# untitled_1.net
KiCad netlist of a schematic drawn in EAGLE
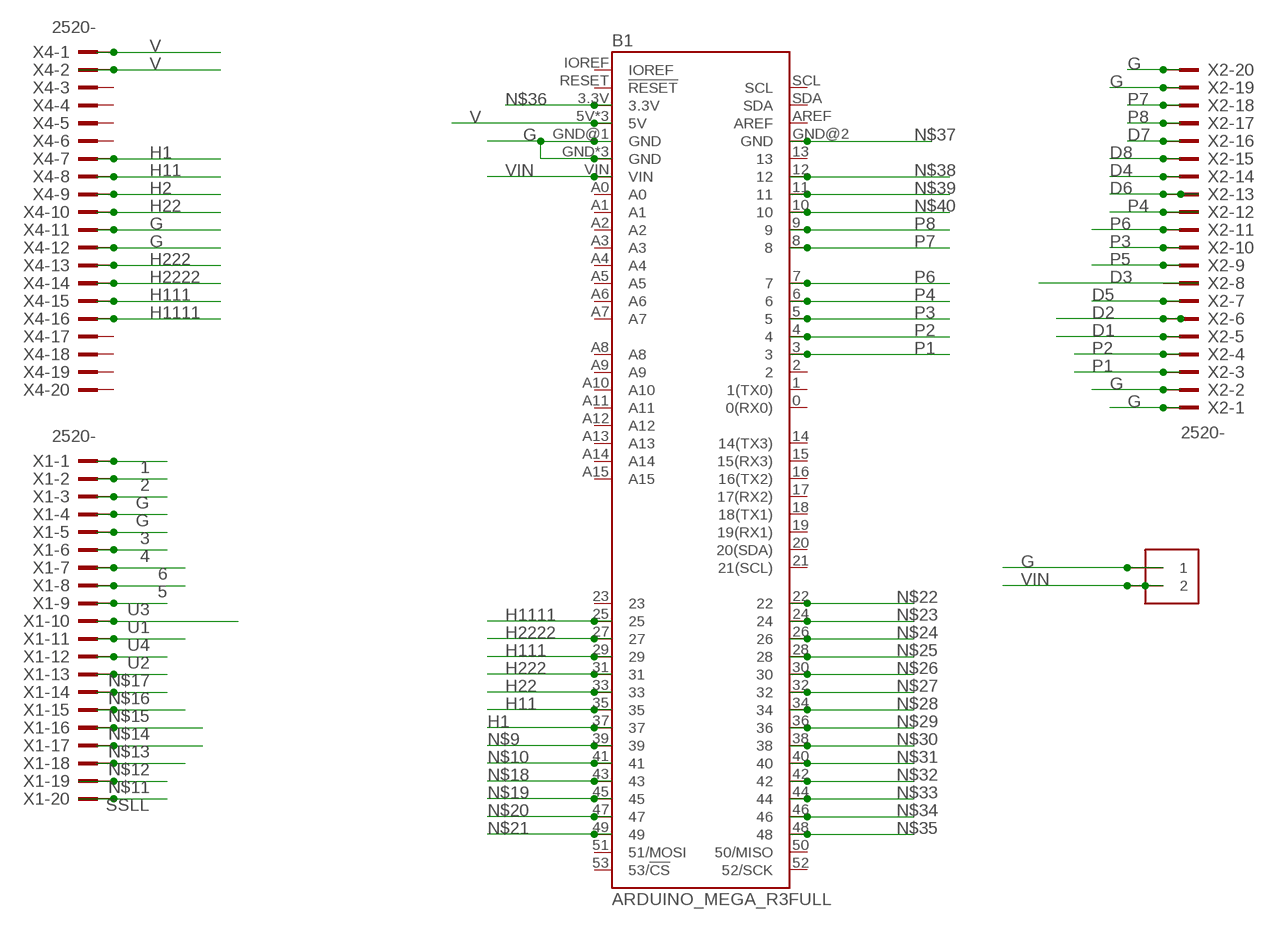
[diagram p0: schematic, sheet 1]

(export (version "E")
  (design (tool "Eeschema 10.0.6"))
  (components
    (comp (ref "B1")
      (value "ARDUINO_MEGA_R3FULL")
      (footprint "eagle-import:ARDUINO_MEGA_NO_SILK")
      (libsource (lib "eagle-import") (part "ARDUINO_MEGA_R3FULL"))
    )
    (comp (ref "J1")
      (value "1X2-3.5MM")
      (footprint "eagle-import:1X2-3.5MM")
      (libsource (lib "eagle-import") (part "1X2-3.5MM"))
    )
    (comp (ref "X1")
      (value "2520-")
      (footprint "eagle-import:PAK100_2500-20")
      (libsource (lib "eagle-import") (part "con-3m_119_2520-"))
    )
    (comp (ref "X2")
      (value "2520-")
      (footprint "eagle-import:PAK100_2500-20")
      (libsource (lib "eagle-import") (part "con-3m_119_2520-"))
    )
    (comp (ref "X4")
      (value "2520-")
      (footprint "eagle-import:PAK100_2500-20")
      (libsource (lib "eagle-import") (part "2520-"))
    )
  )
  (nets
    (net (code "1") (name "/1") (class "Default")
      (node (ref "X1") (pin "1") (pinfunction "KL_1") (pintype "passive"))
    )
    (net (code "2") (name "/2") (class "Default")
      (node (ref "X1") (pin "2") (pinfunction "KL_2") (pintype "passive"))
    )
    (net (code "3") (name "/3") (class "Default")
      (node (ref "X1") (pin "5") (pinfunction "KL_5") (pintype "passive"))
    )
    (net (code "4") (name "/4") (class "Default")
      (node (ref "X1") (pin "6") (pinfunction "KL_6") (pintype "passive"))
    )
    (net (code "5") (name "/5") (class "Default")
      (node (ref "X1") (pin "8") (pinfunction "KL_8") (pintype "passive"))
    )
    (net (code "6") (name "/6") (class "Default")
      (node (ref "X1") (pin "7") (pinfunction "KL_7") (pintype "passive"))
    )
    (net (code "7") (name "/D1") (class "Default")
      (node (ref "X2") (pin "5") (pinfunction "KL_5") (pintype "passive"))
    )
    (net (code "8") (name "/D2") (class "Default")
      (node (ref "X2") (pin "6") (pinfunction "KL_6") (pintype "passive"))
    )
    (net (code "9") (name "/D3") (class "Default")
      (node (ref "X2") (pin "8") (pinfunction "KL_8") (pintype "passive"))
    )
    (net (code "10") (name "/D4") (class "Default")
      (node (ref "X2") (pin "14") (pinfunction "KL_14") (pintype "passive"))
    )
    (net (code "11") (name "/D5") (class "Default")
      (node (ref "X2") (pin "7") (pinfunction "KL_7") (pintype "passive"))
    )
    (net (code "12") (name "/D6") (class "Default")
      (node (ref "X2") (pin "13") (pinfunction "KL_13") (pintype "passive"))
    )
    (net (code "13") (name "/D7") (class "Default")
      (node (ref "X2") (pin "16") (pinfunction "KL_16") (pintype "passive"))
    )
    (net (code "14") (name "/D8") (class "Default")
      (node (ref "X2") (pin "15") (pinfunction "KL_15") (pintype "passive"))
    )
    (net (code "15") (name "/G") (class "Default")
      (node (ref "B1") (pin "GND") (pinfunction "GND_GND") (pintype "bidirectional"))
      (node (ref "B1") (pin "GND@1") (pinfunction "GND_GND@1") (pintype "bidirectional"))
      (node (ref "B1") (pin "GND@3") (pinfunction "GND_GND@3") (pintype "bidirectional"))
      (node (ref "B1") (pin "GND@4") (pinfunction "GND_GND@4") (pintype "bidirectional"))
      (node (ref "J1") (pin "1") (pinfunction "1_1") (pintype "passive"))
      (node (ref "X1") (pin "3") (pinfunction "KL_3") (pintype "passive"))
      (node (ref "X1") (pin "4") (pinfunction "KL_4") (pintype "passive"))
      (node (ref "X2") (pin "1") (pinfunction "KL_1") (pintype "passive"))
      (node (ref "X2") (pin "19") (pinfunction "KL_19") (pintype "passive"))
      (node (ref "X2") (pin "2") (pinfunction "KL_2") (pintype "passive"))
      (node (ref "X2") (pin "20") (pinfunction "KL_20") (pintype "passive"))
      (node (ref "X4") (pin "11") (pinfunction "KL_11") (pintype "passive"))
      (node (ref "X4") (pin "12") (pinfunction "KL_12") (pintype "passive"))
    )
    (net (code "16") (name "/H1") (class "Default")
      (node (ref "B1") (pin "37") (pinfunction "37_37") (pintype "bidirectional"))
      (node (ref "X4") (pin "7") (pinfunction "KL_7") (pintype "passive"))
    )
    (net (code "17") (name "/H2") (class "Default")
      (node (ref "X4") (pin "9") (pinfunction "KL_9") (pintype "passive"))
    )
    (net (code "18") (name "/H11") (class "Default")
      (node (ref "B1") (pin "35") (pinfunction "35_35") (pintype "bidirectional"))
      (node (ref "X4") (pin "8") (pinfunction "KL_8") (pintype "passive"))
    )
    (net (code "19") (name "/H22") (class "Default")
      (node (ref "B1") (pin "33") (pinfunction "33_33") (pintype "bidirectional"))
      (node (ref "X4") (pin "10") (pinfunction "KL_10") (pintype "passive"))
    )
    (net (code "20") (name "/H111") (class "Default")
      (node (ref "B1") (pin "29") (pinfunction "29_29") (pintype "bidirectional"))
      (node (ref "X4") (pin "15") (pinfunction "KL_15") (pintype "passive"))
    )
    (net (code "21") (name "/H222") (class "Default")
      (node (ref "B1") (pin "31") (pinfunction "31_31") (pintype "bidirectional"))
      (node (ref "X4") (pin "13") (pinfunction "KL_13") (pintype "passive"))
    )
    (net (code "22") (name "/H1111") (class "Default")
      (node (ref "B1") (pin "25") (pinfunction "25_25") (pintype "bidirectional"))
      (node (ref "X4") (pin "16") (pinfunction "KL_16") (pintype "passive"))
    )
    (net (code "23") (name "/H2222") (class "Default")
      (node (ref "B1") (pin "27") (pinfunction "27_27") (pintype "bidirectional"))
      (node (ref "X4") (pin "14") (pinfunction "KL_14") (pintype "passive"))
    )
    (net (code "24") (name "/N$9") (class "Default")
      (node (ref "B1") (pin "39") (pinfunction "39_39") (pintype "bidirectional"))
    )
    (net (code "25") (name "/N$10") (class "Default")
      (node (ref "B1") (pin "41") (pinfunction "41_41") (pintype "bidirectional"))
    )
    (net (code "26") (name "/N$11") (class "Default")
      (node (ref "X1") (pin "19") (pinfunction "KL_19") (pintype "passive"))
    )
    (net (code "27") (name "/N$12") (class "Default")
      (node (ref "X1") (pin "18") (pinfunction "KL_18") (pintype "passive"))
    )
    (net (code "28") (name "/N$13") (class "Default")
      (node (ref "X1") (pin "17") (pinfunction "KL_17") (pintype "passive"))
    )
    (net (code "29") (name "/N$14") (class "Default")
      (node (ref "X1") (pin "16") (pinfunction "KL_16") (pintype "passive"))
    )
    (net (code "30") (name "/N$15") (class "Default")
      (node (ref "X1") (pin "15") (pinfunction "KL_15") (pintype "passive"))
    )
    (net (code "31") (name "/N$16") (class "Default")
      (node (ref "X1") (pin "14") (pinfunction "KL_14") (pintype "passive"))
    )
    (net (code "32") (name "/N$17") (class "Default")
      (node (ref "X1") (pin "13") (pinfunction "KL_13") (pintype "passive"))
    )
    (net (code "33") (name "/N$18") (class "Default")
      (node (ref "B1") (pin "43") (pinfunction "43_43") (pintype "bidirectional"))
    )
    (net (code "34") (name "/N$19") (class "Default")
      (node (ref "B1") (pin "45") (pinfunction "45_45") (pintype "bidirectional"))
    )
    (net (code "35") (name "/N$20") (class "Default")
      (node (ref "B1") (pin "47") (pinfunction "47_47") (pintype "bidirectional"))
    )
    (net (code "36") (name "/N$21") (class "Default")
      (node (ref "B1") (pin "49") (pinfunction "49_49") (pintype "bidirectional"))
    )
    (net (code "37") (name "/N$22") (class "Default")
      (node (ref "B1") (pin "22") (pinfunction "22_22") (pintype "bidirectional"))
    )
    (net (code "38") (name "/N$23") (class "Default")
      (node (ref "B1") (pin "24") (pinfunction "24_24") (pintype "bidirectional"))
    )
    (net (code "39") (name "/N$24") (class "Default")
      (node (ref "B1") (pin "26") (pinfunction "26_26") (pintype "bidirectional"))
    )
    (net (code "40") (name "/N$25") (class "Default")
      (node (ref "B1") (pin "28") (pinfunction "28_28") (pintype "bidirectional"))
    )
    (net (code "41") (name "/N$26") (class "Default")
      (node (ref "B1") (pin "30") (pinfunction "30_30") (pintype "bidirectional"))
    )
    (net (code "42") (name "/N$27") (class "Default")
      (node (ref "B1") (pin "32") (pinfunction "32_32") (pintype "bidirectional"))
    )
    (net (code "43") (name "/N$28") (class "Default")
      (node (ref "B1") (pin "34") (pinfunction "34_34") (pintype "bidirectional"))
    )
    (net (code "44") (name "/N$29") (class "Default")
      (node (ref "B1") (pin "36") (pinfunction "36_36") (pintype "bidirectional"))
    )
    (net (code "45") (name "/N$30") (class "Default")
      (node (ref "B1") (pin "38") (pinfunction "38_38") (pintype "bidirectional"))
    )
    (net (code "46") (name "/N$31") (class "Default")
      (node (ref "B1") (pin "40") (pinfunction "40_40") (pintype "bidirectional"))
    )
    (net (code "47") (name "/N$32") (class "Default")
      (node (ref "B1") (pin "42") (pinfunction "42_42") (pintype "bidirectional"))
    )
    (net (code "48") (name "/N$33") (class "Default")
      (node (ref "B1") (pin "44") (pinfunction "44_44") (pintype "bidirectional"))
    )
    (net (code "49") (name "/N$34") (class "Default")
      (node (ref "B1") (pin "46") (pinfunction "46_46") (pintype "bidirectional"))
    )
    (net (code "50") (name "/N$35") (class "Default")
      (node (ref "B1") (pin "48") (pinfunction "48_48") (pintype "bidirectional"))
    )
    (net (code "51") (name "/N$36") (class "Default")
      (node (ref "B1") (pin "3.3V") (pinfunction "3.3V_3.3V") (pintype "bidirectional"))
    )
    (net (code "52") (name "/N$37") (class "Default")
      (node (ref "B1") (pin "GND@2") (pinfunction "GND_GND@2") (pintype "bidirectional"))
    )
    (net (code "53") (name "/N$38") (class "Default")
      (node (ref "B1") (pin "12") (pinfunction "12_12") (pintype "bidirectional"))
    )
    (net (code "54") (name "/N$39") (class "Default")
      (node (ref "B1") (pin "11") (pinfunction "11_11") (pintype "bidirectional"))
    )
    (net (code "55") (name "/N$40") (class "Default")
      (node (ref "B1") (pin "10") (pinfunction "10_10") (pintype "bidirectional"))
    )
    (net (code "56") (name "/P1") (class "Default")
      (node (ref "B1") (pin "3") (pinfunction "3_3") (pintype "bidirectional"))
      (node (ref "X2") (pin "3") (pinfunction "KL_3") (pintype "passive"))
    )
    (net (code "57") (name "/P2") (class "Default")
      (node (ref "B1") (pin "4") (pinfunction "4_4") (pintype "bidirectional"))
      (node (ref "X2") (pin "4") (pinfunction "KL_4") (pintype "passive"))
    )
    (net (code "58") (name "/P3") (class "Default")
      (node (ref "B1") (pin "5") (pinfunction "5_5") (pintype "bidirectional"))
      (node (ref "X2") (pin "10") (pinfunction "KL_10") (pintype "passive"))
    )
    (net (code "59") (name "/P4") (class "Default")
      (node (ref "B1") (pin "6") (pinfunction "6_6") (pintype "bidirectional"))
      (node (ref "X2") (pin "12") (pinfunction "KL_12") (pintype "passive"))
    )
    (net (code "60") (name "/P5") (class "Default")
      (node (ref "X2") (pin "9") (pinfunction "KL_9") (pintype "passive"))
    )
    (net (code "61") (name "/P6") (class "Default")
      (node (ref "B1") (pin "7") (pinfunction "7_7") (pintype "bidirectional"))
      (node (ref "X2") (pin "11") (pinfunction "KL_11") (pintype "passive"))
    )
    (net (code "62") (name "/P7") (class "Default")
      (node (ref "B1") (pin "8") (pinfunction "8_8") (pintype "bidirectional"))
      (node (ref "X2") (pin "18") (pinfunction "KL_18") (pintype "passive"))
    )
    (net (code "63") (name "/P8") (class "Default")
      (node (ref "B1") (pin "9") (pinfunction "9_9") (pintype "bidirectional"))
      (node (ref "X2") (pin "17") (pinfunction "KL_17") (pintype "passive"))
    )
    (net (code "64") (name "/SSLL") (class "Default")
      (node (ref "X1") (pin "20") (pinfunction "KL_20") (pintype "passive"))
    )
    (net (code "65") (name "/U1") (class "Default")
      (node (ref "X1") (pin "10") (pinfunction "KL_10") (pintype "passive"))
    )
    (net (code "66") (name "/U2") (class "Default")
      (node (ref "X1") (pin "12") (pinfunction "KL_12") (pintype "passive"))
    )
    (net (code "67") (name "/U3") (class "Default")
      (node (ref "X1") (pin "9") (pinfunction "KL_9") (pintype "passive"))
    )
    (net (code "68") (name "/U4") (class "Default")
      (node (ref "X1") (pin "11") (pinfunction "KL_11") (pintype "passive"))
    )
    (net (code "69") (name "/V") (class "Default")
      (node (ref "B1") (pin "5V") (pinfunction "5V_5V") (pintype "bidirectional"))
      (node (ref "B1") (pin "5V@1") (pinfunction "5V_5V@1") (pintype "bidirectional"))
      (node (ref "B1") (pin "5V@2") (pinfunction "5V_5V@2") (pintype "bidirectional"))
      (node (ref "X4") (pin "1") (pinfunction "KL_1") (pintype "passive"))
      (node (ref "X4") (pin "2") (pinfunction "KL_2") (pintype "passive"))
    )
    (net (code "70") (name "/VIN") (class "Default")
      (node (ref "B1") (pin "VIN") (pinfunction "VIN_VIN") (pintype "bidirectional"))
      (node (ref "J1") (pin "2") (pinfunction "2_2") (pintype "passive"))
    )
    (net (code "71") (name "unconnected-(B1-0(RX0)-Pad0)") (class "Default")
      (node (ref "B1") (pin "0") (pinfunction "0(RX0)_0") (pintype "bidirectional"))
    )
    (net (code "72") (name "unconnected-(B1-1(TX0)-Pad1)") (class "Default")
      (node (ref "B1") (pin "1") (pinfunction "1(TX0)_1") (pintype "bidirectional"))
    )
    (net (code "73") (name "unconnected-(B1-14(TX3)-Pad14)") (class "Default")
      (node (ref "B1") (pin "14") (pinfunction "14(TX3)_14") (pintype "bidirectional"))
    )
    (net (code "74") (name "unconnected-(B1-15(RX3)-Pad15)") (class "Default")
      (node (ref "B1") (pin "15") (pinfunction "15(RX3)_15") (pintype "bidirectional"))
    )
    (net (code "75") (name "unconnected-(B1-16(TX2)-Pad16)") (class "Default")
      (node (ref "B1") (pin "16") (pinfunction "16(TX2)_16") (pintype "bidirectional"))
    )
    (net (code "76") (name "unconnected-(B1-17(RX2)-Pad17)") (class "Default")
      (node (ref "B1") (pin "17") (pinfunction "17(RX2)_17") (pintype "bidirectional"))
    )
    (net (code "77") (name "unconnected-(B1-18(TX1)-Pad18)") (class "Default")
      (node (ref "B1") (pin "18") (pinfunction "18(TX1)_18") (pintype "bidirectional"))
    )
    (net (code "78") (name "unconnected-(B1-19(RX1)-Pad19)") (class "Default")
      (node (ref "B1") (pin "19") (pinfunction "19(RX1)_19") (pintype "bidirectional"))
    )
    (net (code "79") (name "unconnected-(B1-20(SDA)-Pad20)") (class "Default")
      (node (ref "B1") (pin "20") (pinfunction "20(SDA)_20") (pintype "bidirectional"))
    )
    (net (code "80") (name "unconnected-(B1-21(SCL)-Pad21)") (class "Default")
      (node (ref "B1") (pin "21") (pinfunction "21(SCL)_21") (pintype "bidirectional"))
    )
    (net (code "81") (name "unconnected-(B1-50{slash}MISO-Pad50)") (class "Default")
      (node (ref "B1") (pin "50") (pinfunction "50/MISO_50") (pintype "bidirectional"))
    )
    (net (code "82") (name "unconnected-(B1-51{slash}MOSI-Pad51)") (class "Default")
      (node (ref "B1") (pin "51") (pinfunction "51/MOSI_51") (pintype "bidirectional"))
    )
    (net (code "83") (name "unconnected-(B1-52{slash}SCK-Pad52)") (class "Default")
      (node (ref "B1") (pin "52") (pinfunction "52/SCK_52") (pintype "bidirectional"))
    )
    (net (code "84") (name "unconnected-(B1-53{slash}~{CS}-Pad53)") (class "Default")
      (node (ref "B1") (pin "53") (pinfunction "53/~{CS}_53") (pintype "bidirectional"))
    )
    (net (code "85") (name "unconnected-(B1-Pad2)") (class "Default")
      (node (ref "B1") (pin "2") (pinfunction "2_2") (pintype "bidirectional"))
    )
    (net (code "86") (name "unconnected-(B1-Pad13)") (class "Default")
      (node (ref "B1") (pin "13") (pinfunction "13_13") (pintype "bidirectional"))
    )
    (net (code "87") (name "unconnected-(B1-Pad23)") (class "Default")
      (node (ref "B1") (pin "23") (pinfunction "23_23") (pintype "bidirectional"))
    )
    (net (code "88") (name "unconnected-(B1-PadA0)") (class "Default")
      (node (ref "B1") (pin "A0") (pinfunction "A0_A0") (pintype "bidirectional"))
    )
    (net (code "89") (name "unconnected-(B1-PadA1)") (class "Default")
      (node (ref "B1") (pin "A1") (pinfunction "A1_A1") (pintype "bidirectional"))
    )
    (net (code "90") (name "unconnected-(B1-PadA2)") (class "Default")
      (node (ref "B1") (pin "A2") (pinfunction "A2_A2") (pintype "bidirectional"))
    )
    (net (code "91") (name "unconnected-(B1-PadA3)") (class "Default")
      (node (ref "B1") (pin "A3") (pinfunction "A3_A3") (pintype "bidirectional"))
    )
    (net (code "92") (name "unconnected-(B1-PadA4)") (class "Default")
      (node (ref "B1") (pin "A4") (pinfunction "A4_A4") (pintype "bidirectional"))
    )
    (net (code "93") (name "unconnected-(B1-PadA5)") (class "Default")
      (node (ref "B1") (pin "A5") (pinfunction "A5_A5") (pintype "bidirectional"))
    )
    (net (code "94") (name "unconnected-(B1-PadA6)") (class "Default")
      (node (ref "B1") (pin "A6") (pinfunction "A6_A6") (pintype "bidirectional"))
    )
    (net (code "95") (name "unconnected-(B1-PadA7)") (class "Default")
      (node (ref "B1") (pin "A7") (pinfunction "A7_A7") (pintype "bidirectional"))
    )
    (net (code "96") (name "unconnected-(B1-PadA8)") (class "Default")
      (node (ref "B1") (pin "A8") (pinfunction "A8_A8") (pintype "bidirectional"))
    )
    (net (code "97") (name "unconnected-(B1-PadA9)") (class "Default")
      (node (ref "B1") (pin "A9") (pinfunction "A9_A9") (pintype "bidirectional"))
    )
    (net (code "98") (name "unconnected-(B1-PadA10)") (class "Default")
      (node (ref "B1") (pin "A10") (pinfunction "A10_A10") (pintype "bidirectional"))
    )
    (net (code "99") (name "unconnected-(B1-PadA11)") (class "Default")
      (node (ref "B1") (pin "A11") (pinfunction "A11_A11") (pintype "bidirectional"))
    )
    (net (code "100") (name "unconnected-(B1-PadA12)") (class "Default")
      (node (ref "B1") (pin "A12") (pinfunction "A12_A12") (pintype "bidirectional"))
    )
    (net (code "101") (name "unconnected-(B1-PadA13)") (class "Default")
      (node (ref "B1") (pin "A13") (pinfunction "A13_A13") (pintype "bidirectional"))
    )
    (net (code "102") (name "unconnected-(B1-PadA14)") (class "Default")
      (node (ref "B1") (pin "A14") (pinfunction "A14_A14") (pintype "bidirectional"))
    )
    (net (code "103") (name "unconnected-(B1-PadA15)") (class "Default")
      (node (ref "B1") (pin "A15") (pinfunction "A15_A15") (pintype "bidirectional"))
    )
    (net (code "104") (name "unconnected-(B1-PadAREF)") (class "Default")
      (node (ref "B1") (pin "AREF") (pinfunction "AREF_AREF") (pintype "bidirectional"))
    )
    (net (code "105") (name "unconnected-(B1-PadIOREF)") (class "Default")
      (node (ref "B1") (pin "IOREF") (pinfunction "IOREF_IOREF") (pintype "bidirectional"))
    )
    (net (code "106") (name "unconnected-(B1-PadSCL)") (class "Default")
      (node (ref "B1") (pin "SCL") (pinfunction "SCL_SCL") (pintype "bidirectional"))
    )
    (net (code "107") (name "unconnected-(B1-PadSDA)") (class "Default")
      (node (ref "B1") (pin "SDA") (pinfunction "SDA_SDA") (pintype "bidirectional"))
    )
    (net (code "108") (name "unconnected-(B1-~{RESET}-PadRESET)") (class "Default")
      (node (ref "B1") (pin "RESET") (pinfunction "~{RESET}_RESET") (pintype "bidirectional"))
    )
    (net (code "109") (name "unconnected-(X4I-KL-Pad17)") (class "Default")
      (node (ref "X4") (pin "17") (pinfunction "KL_17") (pintype "passive"))
    )
    (net (code "110") (name "unconnected-(X4J-KL-Pad18)") (class "Default")
      (node (ref "X4") (pin "18") (pinfunction "KL_18") (pintype "passive"))
    )
    (net (code "111") (name "unconnected-(X4K-KL-Pad19)") (class "Default")
      (node (ref "X4") (pin "19") (pinfunction "KL_19") (pintype "passive"))
    )
    (net (code "112") (name "unconnected-(X4M-KL-Pad20)") (class "Default")
      (node (ref "X4") (pin "20") (pinfunction "KL_20") (pintype "passive"))
    )
    (net (code "113") (name "unconnected-(X4N-KL-Pad3)") (class "Default")
      (node (ref "X4") (pin "3") (pinfunction "KL_3") (pintype "passive"))
    )
    (net (code "114") (name "unconnected-(X4O-KL-Pad4)") (class "Default")
      (node (ref "X4") (pin "4") (pinfunction "KL_4") (pintype "passive"))
    )
    (net (code "115") (name "unconnected-(X4P-KL-Pad5)") (class "Default")
      (node (ref "X4") (pin "5") (pinfunction "KL_5") (pintype "passive"))
    )
    (net (code "116") (name "unconnected-(X4Q-KL-Pad6)") (class "Default")
      (node (ref "X4") (pin "6") (pinfunction "KL_6") (pintype "passive"))
    )
  )
)
